# ADXL344.net
KiCad netlist of a schematic drawn in EAGLE
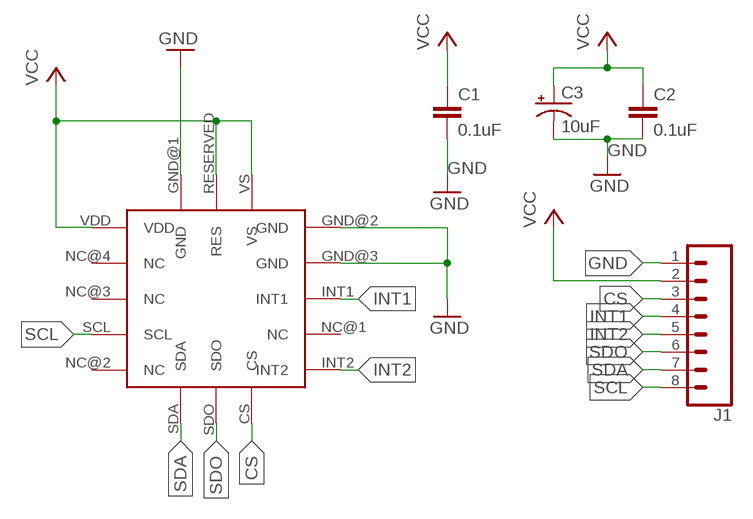
[diagram p0: schematic, sheet 1]

(export (version "E")
  (design (tool "Eeschema 10.0.6"))
  (components
    (comp (ref "ADXL1")
      (value "ADXL344ADXL-C")
      (footprint "eagle-import:ADXL-C")
      (libsource (lib "eagle-import") (part "ADXL344ADXL-C"))
    )
    (comp (ref "C1")
      (value "0.1uF")
      (footprint "eagle-import:0603")
      (libsource (lib "eagle-import") (part "0.1UF-0603-25V-5%"))
    )
    (comp (ref "C2")
      (value "0.1uF")
      (footprint "eagle-import:0603")
      (libsource (lib "eagle-import") (part "0.1UF-0603-25V-5%"))
    )
    (comp (ref "C3")
      (value "10uF")
      (footprint "eagle-import:0603-POLAR")
      (libsource (lib "eagle-import") (part "10UF-POLAR-0603-6.3V-20%(TANT)"))
    )
    (comp (ref "J1")
      (value "CONN_08\"")
      (footprint "eagle-import:1X08")
      (libsource (lib "eagle-import") (part "CONN_08{dblquote}"))
    )
  )
  (nets
    (net (code "1") (name "CS") (class "Default")
      (node (ref "ADXL1") (pin "CS") (pinfunction "CS_CS") (pintype "bidirectional"))
      (node (ref "J1") (pin "3") (pinfunction "3_3") (pintype "passive"))
    )
    (net (code "2") (name "GND") (class "Default")
      (node (ref "ADXL1") (pin "GND@1") (pinfunction "GND_GND@1") (pintype "bidirectional"))
      (node (ref "ADXL1") (pin "GND@2") (pinfunction "GND_GND@2") (pintype "bidirectional"))
      (node (ref "ADXL1") (pin "GND@3") (pinfunction "GND_GND@3") (pintype "bidirectional"))
      (node (ref "C1") (pin "2") (pinfunction "2_2") (pintype "passive"))
      (node (ref "C2") (pin "2") (pinfunction "2_2") (pintype "passive"))
      (node (ref "C3") (pin "-") (pinfunction "-_-") (pintype "passive"))
      (node (ref "J1") (pin "1") (pinfunction "1_1") (pintype "passive"))
    )
    (net (code "3") (name "INT1") (class "Default")
      (node (ref "ADXL1") (pin "INT1") (pinfunction "INT1_INT1") (pintype "bidirectional"))
      (node (ref "J1") (pin "4") (pinfunction "4_4") (pintype "passive"))
    )
    (net (code "4") (name "INT2") (class "Default")
      (node (ref "ADXL1") (pin "INT2") (pinfunction "INT2_INT2") (pintype "bidirectional"))
      (node (ref "J1") (pin "5") (pinfunction "5_5") (pintype "passive"))
    )
    (net (code "5") (name "SCL") (class "Default")
      (node (ref "ADXL1") (pin "SCL") (pinfunction "SCL_SCL") (pintype "bidirectional"))
      (node (ref "J1") (pin "8") (pinfunction "8_8") (pintype "passive"))
    )
    (net (code "6") (name "SDA") (class "Default")
      (node (ref "ADXL1") (pin "SDA") (pinfunction "SDA_SDA") (pintype "bidirectional"))
      (node (ref "J1") (pin "7") (pinfunction "7_7") (pintype "passive"))
    )
    (net (code "7") (name "SDO") (class "Default")
      (node (ref "ADXL1") (pin "SDO") (pinfunction "SDO_SDO") (pintype "bidirectional"))
      (node (ref "J1") (pin "6") (pinfunction "6_6") (pintype "passive"))
    )
    (net (code "8") (name "VCC") (class "Default")
      (node (ref "ADXL1") (pin "RESERVED") (pinfunction "RES_RESERVED") (pintype "bidirectional"))
      (node (ref "ADXL1") (pin "VDD") (pinfunction "VDD_VDD") (pintype "bidirectional"))
      (node (ref "ADXL1") (pin "VS") (pinfunction "VS_VS") (pintype "bidirectional"))
      (node (ref "C1") (pin "1") (pinfunction "1_1") (pintype "passive"))
      (node (ref "C2") (pin "1") (pinfunction "1_1") (pintype "passive"))
      (node (ref "C3") (pin "+") (pinfunction "+_+") (pintype "passive"))
      (node (ref "J1") (pin "2") (pinfunction "2_2") (pintype "passive"))
    )
    (net (code "9") (name "unconnected-(ADXL1-NC-PadNC@1)") (class "Default")
      (node (ref "ADXL1") (pin "NC@1") (pinfunction "NC_NC@1") (pintype "bidirectional"))
    )
    (net (code "10") (name "unconnected-(ADXL1-NC-PadNC@2)") (class "Default")
      (node (ref "ADXL1") (pin "NC@2") (pinfunction "NC_NC@2") (pintype "bidirectional"))
    )
    (net (code "11") (name "unconnected-(ADXL1-NC-PadNC@3)") (class "Default")
      (node (ref "ADXL1") (pin "NC@3") (pinfunction "NC_NC@3") (pintype "bidirectional"))
    )
    (net (code "12") (name "unconnected-(ADXL1-NC-PadNC@4)") (class "Default")
      (node (ref "ADXL1") (pin "NC@4") (pinfunction "NC_NC@4") (pintype "bidirectional"))
    )
  )
)
